# SG_Feedback.net
KiCad netlist of a schematic drawn in Altium Designer
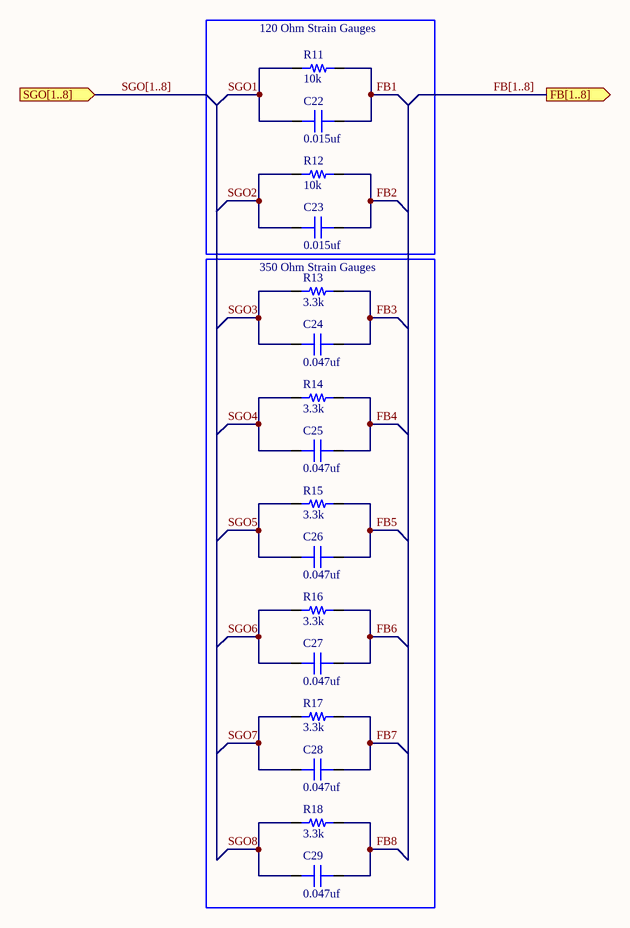
[diagram p0: SG_Feedback.SchDoc]

(export (version "E")
  (design (tool "Eeschema 10.0.6"))
  (components
    (comp (ref "C22")
      (value "0.015uf")
      (footprint "CAP 0603/1608")
      (fields
        (field (name "Comment") "Capacitor MLCC 0.015uf 25V CAP 0603/1608")
        (field (name "CREATED_BY") "Nick Mah")
      )
      (libsource (lib "Altium-Lib") (part "Capacitor"))
    )
    (comp (ref "C23")
      (value "0.015uf")
      (footprint "CAP 0603/1608")
      (fields
        (field (name "Comment") "Capacitor MLCC 0.015uf 25V CAP 0603/1608")
        (field (name "CREATED_BY") "Nick Mah")
      )
      (libsource (lib "Altium-Lib") (part "Capacitor"))
    )
    (comp (ref "C24")
      (value "0.047uf")
      (footprint "CAP 0603/1608")
      (fields
        (field (name "Comment") "Capacitor MLCC 0.047uf 50V CAP 0603/1608")
        (field (name "CREATED_BY") "Nick Mah")
      )
      (libsource (lib "Altium-Lib") (part "Capacitor"))
    )
    (comp (ref "C25")
      (value "0.047uf")
      (footprint "CAP 0603/1608")
      (fields
        (field (name "Comment") "Capacitor MLCC 0.047uf 50V CAP 0603/1608")
        (field (name "CREATED_BY") "Nick Mah")
      )
      (libsource (lib "Altium-Lib") (part "Capacitor"))
    )
    (comp (ref "C26")
      (value "0.047uf")
      (footprint "CAP 0603/1608")
      (fields
        (field (name "Comment") "Capacitor MLCC 0.047uf 50V CAP 0603/1608")
        (field (name "CREATED_BY") "Nick Mah")
      )
      (libsource (lib "Altium-Lib") (part "Capacitor"))
    )
    (comp (ref "C27")
      (value "0.047uf")
      (footprint "CAP 0603/1608")
      (fields
        (field (name "Comment") "Capacitor MLCC 0.047uf 50V CAP 0603/1608")
        (field (name "CREATED_BY") "Nick Mah")
      )
      (libsource (lib "Altium-Lib") (part "Capacitor"))
    )
    (comp (ref "C28")
      (value "0.047uf")
      (footprint "CAP 0603/1608")
      (fields
        (field (name "Comment") "Capacitor MLCC 0.047uf 50V CAP 0603/1608")
        (field (name "CREATED_BY") "Nick Mah")
      )
      (libsource (lib "Altium-Lib") (part "Capacitor"))
    )
    (comp (ref "C29")
      (value "0.047uf")
      (footprint "CAP 0603/1608")
      (fields
        (field (name "Comment") "Capacitor MLCC 0.047uf 50V CAP 0603/1608")
        (field (name "CREATED_BY") "Nick Mah")
      )
      (libsource (lib "Altium-Lib") (part "Capacitor"))
    )
    (comp (ref "R11")
      (value "10k")
      (footprint "RES 0603/1608")
      (fields
        (field (name "TOLERANCE") "1%")
        (field (name "POWER") "1/10W")
        (field (name "Comment") "Resistor 10k 0603 1/10W 1%")
        (field (name "CREATED_BY") "Nick Mah")
      )
      (libsource (lib "Altium-Lib") (part "Resistor"))
    )
    (comp (ref "R12")
      (value "10k")
      (footprint "RES 0603/1608")
      (fields
        (field (name "TOLERANCE") "1%")
        (field (name "POWER") "1/10W")
        (field (name "Comment") "Resistor 10k 0603 1/10W 1%")
        (field (name "CREATED_BY") "Nick Mah")
      )
      (libsource (lib "Altium-Lib") (part "Resistor"))
    )
    (comp (ref "R13")
      (value "3.3k")
      (footprint "RES 0603/1608")
      (fields
        (field (name "TOLERANCE") "5%")
        (field (name "POWER") "1/10W")
        (field (name "Comment") "Resistor 3.3k 0603 1/10W 5%")
        (field (name "CREATED_BY") "Nick Mah")
      )
      (libsource (lib "Altium-Lib") (part "Resistor"))
    )
    (comp (ref "R14")
      (value "3.3k")
      (footprint "RES 0603/1608")
      (fields
        (field (name "TOLERANCE") "5%")
        (field (name "POWER") "1/10W")
        (field (name "Comment") "Resistor 3.3k 0603 1/10W 5%")
        (field (name "CREATED_BY") "Nick Mah")
      )
      (libsource (lib "Altium-Lib") (part "Resistor"))
    )
    (comp (ref "R15")
      (value "3.3k")
      (footprint "RES 0603/1608")
      (fields
        (field (name "TOLERANCE") "5%")
        (field (name "POWER") "1/10W")
        (field (name "Comment") "Resistor 3.3k 0603 1/10W 5%")
        (field (name "CREATED_BY") "Nick Mah")
      )
      (libsource (lib "Altium-Lib") (part "Resistor"))
    )
    (comp (ref "R16")
      (value "3.3k")
      (footprint "RES 0603/1608")
      (fields
        (field (name "TOLERANCE") "5%")
        (field (name "POWER") "1/10W")
        (field (name "Comment") "Resistor 3.3k 0603 1/10W 5%")
        (field (name "CREATED_BY") "Nick Mah")
      )
      (libsource (lib "Altium-Lib") (part "Resistor"))
    )
    (comp (ref "R17")
      (value "3.3k")
      (footprint "RES 0603/1608")
      (fields
        (field (name "TOLERANCE") "5%")
        (field (name "POWER") "1/10W")
        (field (name "Comment") "Resistor 3.3k 0603 1/10W 5%")
        (field (name "CREATED_BY") "Nick Mah")
      )
      (libsource (lib "Altium-Lib") (part "Resistor"))
    )
    (comp (ref "R18")
      (value "3.3k")
      (footprint "RES 0603/1608")
      (fields
        (field (name "TOLERANCE") "5%")
        (field (name "POWER") "1/10W")
        (field (name "Comment") "Resistor 3.3k 0603 1/10W 5%")
        (field (name "CREATED_BY") "Nick Mah")
      )
      (libsource (lib "Altium-Lib") (part "Resistor"))
    )
  )
  (nets
    (net (code "1") (name "/FB1") (class "Default")
      (node (ref "C22") (pin "2") (pinfunction "2_2") (pintype "passive"))
      (node (ref "R11") (pin "2") (pinfunction "2_2") (pintype "passive"))
    )
    (net (code "2") (name "/FB2") (class "Default")
      (node (ref "C23") (pin "2") (pinfunction "2_2") (pintype "passive"))
      (node (ref "R12") (pin "2") (pinfunction "2_2") (pintype "passive"))
    )
    (net (code "3") (name "/FB3") (class "Default")
      (node (ref "C24") (pin "2") (pinfunction "2_2") (pintype "passive"))
      (node (ref "R13") (pin "2") (pinfunction "2_2") (pintype "passive"))
    )
    (net (code "4") (name "/FB4") (class "Default")
      (node (ref "C25") (pin "2") (pinfunction "2_2") (pintype "passive"))
      (node (ref "R14") (pin "2") (pinfunction "2_2") (pintype "passive"))
    )
    (net (code "5") (name "/FB5") (class "Default")
      (node (ref "C26") (pin "2") (pinfunction "2_2") (pintype "passive"))
      (node (ref "R15") (pin "2") (pinfunction "2_2") (pintype "passive"))
    )
    (net (code "6") (name "/FB6") (class "Default")
      (node (ref "C27") (pin "2") (pinfunction "2_2") (pintype "passive"))
      (node (ref "R16") (pin "2") (pinfunction "2_2") (pintype "passive"))
    )
    (net (code "7") (name "/FB7") (class "Default")
      (node (ref "C28") (pin "2") (pinfunction "2_2") (pintype "passive"))
      (node (ref "R17") (pin "2") (pinfunction "2_2") (pintype "passive"))
    )
    (net (code "8") (name "/FB8") (class "Default")
      (node (ref "C29") (pin "2") (pinfunction "2_2") (pintype "passive"))
      (node (ref "R18") (pin "2") (pinfunction "2_2") (pintype "passive"))
    )
    (net (code "10") (name "/SGO1") (class "Default")
      (node (ref "C22") (pin "1") (pinfunction "1_1") (pintype "passive"))
      (node (ref "R11") (pin "1") (pinfunction "1_1") (pintype "passive"))
    )
    (net (code "11") (name "/SGO2") (class "Default")
      (node (ref "C23") (pin "1") (pinfunction "1_1") (pintype "passive"))
      (node (ref "R12") (pin "1") (pinfunction "1_1") (pintype "passive"))
    )
    (net (code "12") (name "/SGO3") (class "Default")
      (node (ref "C24") (pin "1") (pinfunction "1_1") (pintype "passive"))
      (node (ref "R13") (pin "1") (pinfunction "1_1") (pintype "passive"))
    )
    (net (code "13") (name "/SGO4") (class "Default")
      (node (ref "C25") (pin "1") (pinfunction "1_1") (pintype "passive"))
      (node (ref "R14") (pin "1") (pinfunction "1_1") (pintype "passive"))
    )
    (net (code "14") (name "/SGO5") (class "Default")
      (node (ref "C26") (pin "1") (pinfunction "1_1") (pintype "passive"))
      (node (ref "R15") (pin "1") (pinfunction "1_1") (pintype "passive"))
    )
    (net (code "15") (name "/SGO6") (class "Default")
      (node (ref "C27") (pin "1") (pinfunction "1_1") (pintype "passive"))
      (node (ref "R16") (pin "1") (pinfunction "1_1") (pintype "passive"))
    )
    (net (code "16") (name "/SGO7") (class "Default")
      (node (ref "C28") (pin "1") (pinfunction "1_1") (pintype "passive"))
      (node (ref "R17") (pin "1") (pinfunction "1_1") (pintype "passive"))
    )
    (net (code "17") (name "/SGO8") (class "Default")
      (node (ref "C29") (pin "1") (pinfunction "1_1") (pintype "passive"))
      (node (ref "R18") (pin "1") (pinfunction "1_1") (pintype "passive"))
    )
  )
)
